# dc26_maneki-neko_badge_page01_20180626.net
KiCad netlist of a schematic drawn in EAGLE
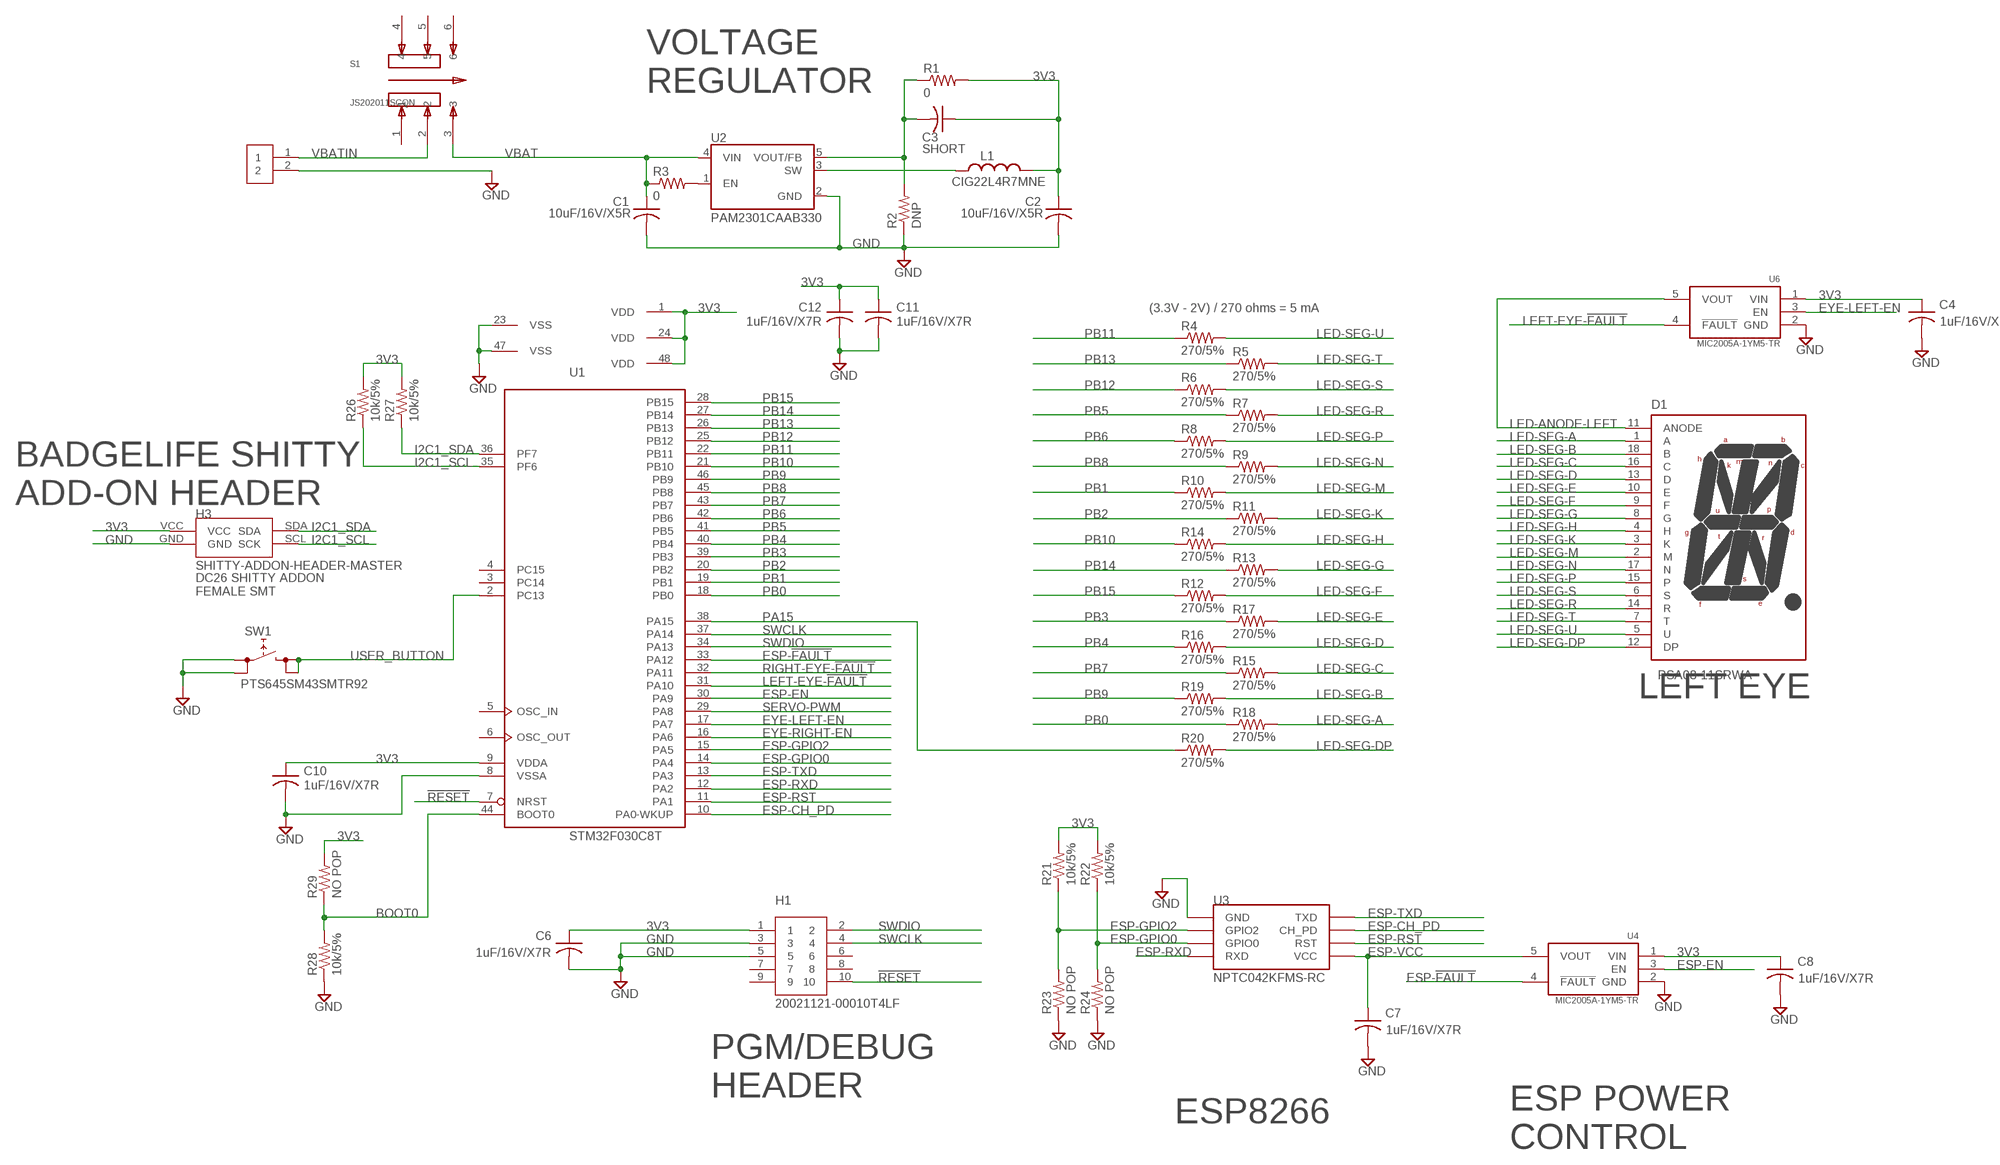
[diagram p0: schematic, sheet 1, part 1 of 2]
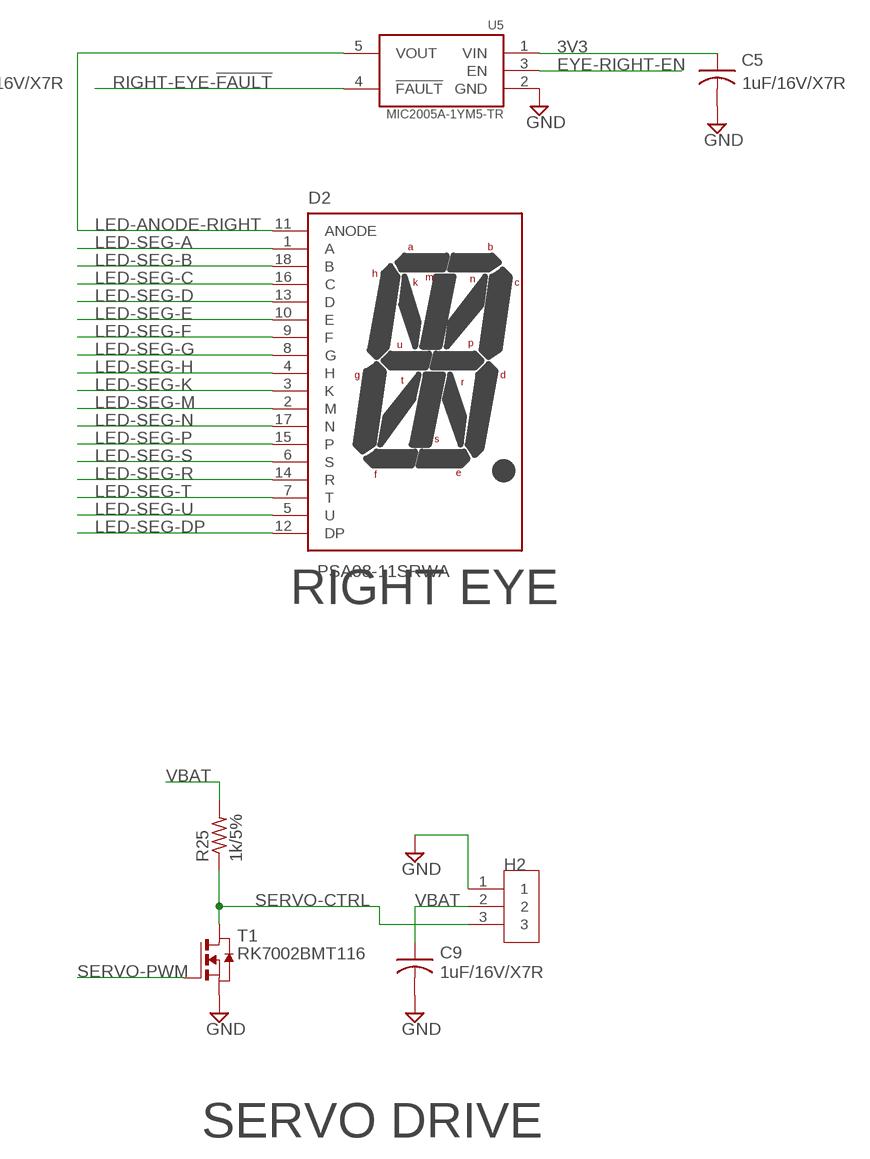
[diagram p1: schematic, sheet 1, part 2 of 2]

(export (version "E")
  (design (tool "Eeschema 10.0.6"))
  (components
    (comp (ref "C1")
      (value "10uF/16V/X5R")
      (footprint "eagle-import:C0805")
      (libsource (lib "eagle-import") (part "C-USC0805"))
    )
    (comp (ref "C2")
      (value "10uF/16V/X5R")
      (footprint "eagle-import:C0805")
      (libsource (lib "eagle-import") (part "C-USC0805"))
    )
    (comp (ref "C3")
      (value "SHORT")
      (footprint "eagle-import:C0805")
      (libsource (lib "eagle-import") (part "C-USC0805"))
    )
    (comp (ref "C4")
      (value "1uF/16V/X7R")
      (footprint "eagle-import:C0805")
      (libsource (lib "eagle-import") (part "C-USC0805"))
    )
    (comp (ref "C5")
      (value "1uF/16V/X7R")
      (footprint "eagle-import:C0805")
      (libsource (lib "eagle-import") (part "C-USC0805"))
    )
    (comp (ref "C6")
      (value "1uF/16V/X7R")
      (footprint "eagle-import:C0805")
      (libsource (lib "eagle-import") (part "C-USC0805"))
    )
    (comp (ref "C7")
      (value "1uF/16V/X7R")
      (footprint "eagle-import:C0805")
      (libsource (lib "eagle-import") (part "C-USC0805"))
    )
    (comp (ref "C8")
      (value "1uF/16V/X7R")
      (footprint "eagle-import:C0805")
      (libsource (lib "eagle-import") (part "C-USC0805"))
    )
    (comp (ref "C9")
      (value "1uF/16V/X7R")
      (footprint "eagle-import:C0805")
      (libsource (lib "eagle-import") (part "C-USC0805"))
    )
    (comp (ref "C10")
      (value "1uF/16V/X7R")
      (footprint "eagle-import:C0805")
      (libsource (lib "eagle-import") (part "C-USC0805"))
    )
    (comp (ref "C11")
      (value "1uF/16V/X7R")
      (footprint "eagle-import:C0805")
      (libsource (lib "eagle-import") (part "C-USC0805"))
    )
    (comp (ref "C12")
      (value "1uF/16V/X7R")
      (footprint "eagle-import:C0805")
      (libsource (lib "eagle-import") (part "C-USC0805"))
    )
    (comp (ref "D1")
      (value "PSA08-11SRWA")
      (footprint "eagle-import:PSA08-11SRWA")
      (libsource (lib "eagle-import") (part "PSA08-11SRWA"))
    )
    (comp (ref "D2")
      (value "PSA08-11SRWA")
      (footprint "eagle-import:PSA08-11SRWA")
      (libsource (lib "eagle-import") (part "PSA08-11SRWA"))
    )
    (comp (ref "H1")
      (value "20021121-00010T4LF")
      (footprint "eagle-import:20021121-00010T4LF")
      (libsource (lib "eagle-import") (part "20021121-00010T4LF"))
    )
    (comp (ref "H2")
      (value "M20-8890345R")
      (footprint "eagle-import:M20-8890345R")
      (libsource (lib "eagle-import") (part "M20-8890345R"))
    )
    (comp (ref "H3")
      (value "SHITTY-ADDON-HEADER-MASTER")
      (footprint "eagle-import:2X2-0.1INCH-FEMALE-SMT")
      (libsource (lib "eagle-import") (part "SHITTY-ADDON-HEADER-MASTER"))
    )
    (comp (ref "L1")
      (value "CIG22L4R7MNE")
      (footprint "eagle-import:L-1008-US")
      (libsource (lib "eagle-import") (part "CIG22L4R7MNE"))
    )
    (comp (ref "R1")
      (value "0")
      (footprint "eagle-import:R0805")
      (libsource (lib "eagle-import") (part "R-US_R0805"))
    )
    (comp (ref "R2")
      (value "DNP")
      (footprint "eagle-import:R0805")
      (libsource (lib "eagle-import") (part "R-US_R0805"))
    )
    (comp (ref "R3")
      (value "0")
      (footprint "eagle-import:R0805")
      (libsource (lib "eagle-import") (part "R-US_R0805"))
    )
    (comp (ref "R4")
      (value "270/5%")
      (footprint "eagle-import:R0805")
      (libsource (lib "eagle-import") (part "R-US_R0805"))
    )
    (comp (ref "R5")
      (value "270/5%")
      (footprint "eagle-import:R0805")
      (libsource (lib "eagle-import") (part "R-US_R0805"))
    )
    (comp (ref "R6")
      (value "270/5%")
      (footprint "eagle-import:R0805")
      (libsource (lib "eagle-import") (part "R-US_R0805"))
    )
    (comp (ref "R7")
      (value "270/5%")
      (footprint "eagle-import:R0805")
      (libsource (lib "eagle-import") (part "R-US_R0805"))
    )
    (comp (ref "R8")
      (value "270/5%")
      (footprint "eagle-import:R0805")
      (libsource (lib "eagle-import") (part "R-US_R0805"))
    )
    (comp (ref "R9")
      (value "270/5%")
      (footprint "eagle-import:R0805")
      (libsource (lib "eagle-import") (part "R-US_R0805"))
    )
    (comp (ref "R10")
      (value "270/5%")
      (footprint "eagle-import:R0805")
      (libsource (lib "eagle-import") (part "R-US_R0805"))
    )
    (comp (ref "R11")
      (value "270/5%")
      (footprint "eagle-import:R0805")
      (libsource (lib "eagle-import") (part "R-US_R0805"))
    )
    (comp (ref "R12")
      (value "270/5%")
      (footprint "eagle-import:R0805")
      (libsource (lib "eagle-import") (part "R-US_R0805"))
    )
    (comp (ref "R13")
      (value "270/5%")
      (footprint "eagle-import:R0805")
      (libsource (lib "eagle-import") (part "R-US_R0805"))
    )
    (comp (ref "R14")
      (value "270/5%")
      (footprint "eagle-import:R0805")
      (libsource (lib "eagle-import") (part "R-US_R0805"))
    )
    (comp (ref "R15")
      (value "270/5%")
      (footprint "eagle-import:R0805")
      (libsource (lib "eagle-import") (part "R-US_R0805"))
    )
    (comp (ref "R16")
      (value "270/5%")
      (footprint "eagle-import:R0805")
      (libsource (lib "eagle-import") (part "R-US_R0805"))
    )
    (comp (ref "R17")
      (value "270/5%")
      (footprint "eagle-import:R0805")
      (libsource (lib "eagle-import") (part "R-US_R0805"))
    )
    (comp (ref "R18")
      (value "270/5%")
      (footprint "eagle-import:R0805")
      (libsource (lib "eagle-import") (part "R-US_R0805"))
    )
    (comp (ref "R19")
      (value "270/5%")
      (footprint "eagle-import:R0805")
      (libsource (lib "eagle-import") (part "R-US_R0805"))
    )
    (comp (ref "R20")
      (value "270/5%")
      (footprint "eagle-import:R0805")
      (libsource (lib "eagle-import") (part "R-US_R0805"))
    )
    (comp (ref "R21")
      (value "10k/5%")
      (footprint "eagle-import:R0805")
      (libsource (lib "eagle-import") (part "R-US_R0805"))
    )
    (comp (ref "R22")
      (value "10k/5%")
      (footprint "eagle-import:R0805")
      (libsource (lib "eagle-import") (part "R-US_R0805"))
    )
    (comp (ref "R23")
      (value "NO POP")
      (footprint "eagle-import:R0805")
      (libsource (lib "eagle-import") (part "R-US_R0805"))
    )
    (comp (ref "R24")
      (value "NO POP")
      (footprint "eagle-import:R0805")
      (libsource (lib "eagle-import") (part "R-US_R0805"))
    )
    (comp (ref "R25")
      (value "1k/5%")
      (footprint "eagle-import:R0805")
      (libsource (lib "eagle-import") (part "R-US_R0805"))
    )
    (comp (ref "R26")
      (value "10k/5%")
      (footprint "eagle-import:R0805")
      (libsource (lib "eagle-import") (part "R-US_R0805"))
    )
    (comp (ref "R27")
      (value "10k/5%")
      (footprint "eagle-import:R0805")
      (libsource (lib "eagle-import") (part "R-US_R0805"))
    )
    (comp (ref "R28")
      (value "10k/5%")
      (footprint "eagle-import:R0805")
      (libsource (lib "eagle-import") (part "R-US_R0805"))
    )
    (comp (ref "R29")
      (value "NO POP")
      (footprint "eagle-import:R0805")
      (libsource (lib "eagle-import") (part "R-US_R0805"))
    )
    (comp (ref "S1")
      (value "JS202011SCQN")
      (footprint "eagle-import:SW_JS202011SCQN")
      (fields (field (name "MF") "C&K Components"))
      (libsource (lib "eagle-import") (part "JS202011SCQN"))
    )
    (comp (ref "SW1")
      (value "PTS645SM43SMTR92")
      (footprint "eagle-import:PTS645SM43SMTR92")
      (libsource (lib "eagle-import") (part "PTS645SM43SMTR92"))
    )
    (comp (ref "T1")
      (value "RK7002BMT116")
      (footprint "eagle-import:SOT-23")
      (libsource (lib "eagle-import") (part "NMOSSOT23"))
    )
    (comp (ref "U$2")
      (value "BATTPADS-SMT")
      (footprint "eagle-import:BATTPADS-SMT")
      (libsource (lib "eagle-import") (part "BATTPADS-SMT"))
    )
    (comp (ref "U1")
      (value "STM32F030C8T")
      (footprint "eagle-import:LQFP48")
      (libsource (lib "eagle-import") (part "STM32F030CT8"))
    )
    (comp (ref "U2")
      (value "PAM2301CAAB330")
      (footprint "eagle-import:SOT95P280X100-5N")
      (libsource (lib "eagle-import") (part "PAM2301CAAB330"))
    )
    (comp (ref "U3")
      (value "NPTC042KFMS-RC")
      (footprint "eagle-import:NPTC042KFMS-RC")
      (libsource (lib "eagle-import") (part "NPTC042KFMS-RC"))
    )
    (comp (ref "U4")
      (value "MIC2005A-1YM5-TR")
      (footprint "eagle-import:SOT95P270X145-5N")
      (libsource (lib "eagle-import") (part "MIC2005A-1YM5-TR"))
    )
    (comp (ref "U5")
      (value "MIC2005A-1YM5-TR")
      (footprint "eagle-import:SOT95P270X145-5N")
      (libsource (lib "eagle-import") (part "MIC2005A-1YM5-TR"))
    )
    (comp (ref "U6")
      (value "MIC2005A-1YM5-TR")
      (footprint "eagle-import:SOT95P270X145-5N")
      (libsource (lib "eagle-import") (part "MIC2005A-1YM5-TR"))
    )
  )
  (nets
    (net (code "1") (name "/3V3") (class "Default")
      (node (ref "C10") (pin "1") (pinfunction "1_1") (pintype "passive"))
      (node (ref "C11") (pin "1") (pinfunction "1_1") (pintype "passive"))
      (node (ref "C12") (pin "1") (pinfunction "1_1") (pintype "passive"))
      (node (ref "C2") (pin "1") (pinfunction "1_1") (pintype "passive"))
      (node (ref "C3") (pin "1") (pinfunction "1_1") (pintype "passive"))
      (node (ref "C4") (pin "1") (pinfunction "1_1") (pintype "passive"))
      (node (ref "C5") (pin "1") (pinfunction "1_1") (pintype "passive"))
      (node (ref "C6") (pin "1") (pinfunction "1_1") (pintype "passive"))
      (node (ref "C8") (pin "1") (pinfunction "1_1") (pintype "passive"))
      (node (ref "H1") (pin "1") (pinfunction "1_1") (pintype "bidirectional"))
      (node (ref "H3") (pin "VCC") (pinfunction "VCC_VCC") (pintype "bidirectional"))
      (node (ref "L1") (pin "P$2") (pinfunction "2_P$2") (pintype "passive"))
      (node (ref "R1") (pin "2") (pinfunction "2_2") (pintype "passive"))
      (node (ref "R21") (pin "2") (pinfunction "2_2") (pintype "passive"))
      (node (ref "R22") (pin "2") (pinfunction "2_2") (pintype "passive"))
      (node (ref "R26") (pin "2") (pinfunction "2_2") (pintype "passive"))
      (node (ref "R27") (pin "2") (pinfunction "2_2") (pintype "passive"))
      (node (ref "R29") (pin "2") (pinfunction "2_2") (pintype "passive"))
      (node (ref "U1") (pin "1") (pinfunction "VDD_1") (pintype "power_in"))
      (node (ref "U1") (pin "24") (pinfunction "VDD_24") (pintype "power_in"))
      (node (ref "U1") (pin "48") (pinfunction "VDD_48") (pintype "power_in"))
      (node (ref "U1") (pin "9") (pinfunction "VDDA_9") (pintype "power_in"))
      (node (ref "U4") (pin "1") (pinfunction "VIN_1") (pintype "bidirectional"))
      (node (ref "U5") (pin "1") (pinfunction "VIN_1") (pintype "bidirectional"))
      (node (ref "U6") (pin "1") (pinfunction "VIN_1") (pintype "bidirectional"))
    )
    (net (code "2") (name "/BOOT0") (class "Default")
      (node (ref "R28") (pin "2") (pinfunction "2_2") (pintype "passive"))
      (node (ref "R29") (pin "1") (pinfunction "1_1") (pintype "passive"))
      (node (ref "U1") (pin "44") (pinfunction "BOOT0_44") (pintype "input"))
    )
    (net (code "3") (name "/ESP-CH_PD") (class "Default")
      (node (ref "U1") (pin "10") (pinfunction "PA0-WKUP_10") (pintype "bidirectional"))
      (node (ref "U3") (pin "3") (pinfunction "CH_PD_3") (pintype "bidirectional"))
    )
    (net (code "4") (name "/ESP-EN") (class "Default")
      (node (ref "U1") (pin "30") (pinfunction "PA9_30") (pintype "bidirectional"))
      (node (ref "U4") (pin "3") (pinfunction "EN_3") (pintype "bidirectional"))
    )
    (net (code "5") (name "/ESP-GPIO0") (class "Default")
      (node (ref "R22") (pin "1") (pinfunction "1_1") (pintype "passive"))
      (node (ref "R24") (pin "2") (pinfunction "2_2") (pintype "passive"))
      (node (ref "U1") (pin "14") (pinfunction "PA4_14") (pintype "bidirectional"))
      (node (ref "U3") (pin "6") (pinfunction "GPIO0_6") (pintype "bidirectional"))
    )
    (net (code "6") (name "/ESP-GPIO2") (class "Default")
      (node (ref "R21") (pin "1") (pinfunction "1_1") (pintype "passive"))
      (node (ref "R23") (pin "2") (pinfunction "2_2") (pintype "passive"))
      (node (ref "U1") (pin "15") (pinfunction "PA5_15") (pintype "bidirectional"))
      (node (ref "U3") (pin "4") (pinfunction "GPIO2_4") (pintype "bidirectional"))
    )
    (net (code "7") (name "/ESP-RST") (class "Default")
      (node (ref "U1") (pin "11") (pinfunction "PA1_11") (pintype "bidirectional"))
      (node (ref "U3") (pin "5") (pinfunction "RST_5") (pintype "bidirectional"))
    )
    (net (code "8") (name "/ESP-RXD") (class "Default")
      (node (ref "U1") (pin "12") (pinfunction "PA2_12") (pintype "bidirectional"))
      (node (ref "U3") (pin "8") (pinfunction "RXD_8") (pintype "bidirectional"))
    )
    (net (code "9") (name "/ESP-TXD") (class "Default")
      (node (ref "U1") (pin "13") (pinfunction "PA3_13") (pintype "bidirectional"))
      (node (ref "U3") (pin "1") (pinfunction "TXD_1") (pintype "bidirectional"))
    )
    (net (code "10") (name "/ESP-VCC") (class "Default")
      (node (ref "C7") (pin "1") (pinfunction "1_1") (pintype "passive"))
      (node (ref "U3") (pin "7") (pinfunction "VCC_7") (pintype "bidirectional"))
      (node (ref "U4") (pin "5") (pinfunction "VOUT_5") (pintype "bidirectional"))
    )
    (net (code "11") (name "/ESP-~{FAULT}") (class "Default")
      (node (ref "U1") (pin "33") (pinfunction "PA12_33") (pintype "bidirectional"))
      (node (ref "U4") (pin "4") (pinfunction "~{FAULT}_4") (pintype "bidirectional"))
    )
    (net (code "12") (name "/EYE-LEFT-EN") (class "Default")
      (node (ref "U1") (pin "17") (pinfunction "PA7_17") (pintype "bidirectional"))
      (node (ref "U6") (pin "3") (pinfunction "EN_3") (pintype "bidirectional"))
    )
    (net (code "13") (name "/EYE-RIGHT-EN") (class "Default")
      (node (ref "U1") (pin "16") (pinfunction "PA6_16") (pintype "bidirectional"))
      (node (ref "U5") (pin "3") (pinfunction "EN_3") (pintype "bidirectional"))
    )
    (net (code "14") (name "/I2C1_SCL") (class "Default")
      (node (ref "H3") (pin "SCL") (pinfunction "SCK_SCL") (pintype "bidirectional"))
      (node (ref "R26") (pin "1") (pinfunction "1_1") (pintype "passive"))
      (node (ref "U1") (pin "35") (pinfunction "PF6_35") (pintype "bidirectional"))
    )
    (net (code "15") (name "/I2C1_SDA") (class "Default")
      (node (ref "H3") (pin "SDA") (pinfunction "SDA_SDA") (pintype "bidirectional"))
      (node (ref "R27") (pin "1") (pinfunction "1_1") (pintype "passive"))
      (node (ref "U1") (pin "36") (pinfunction "PF7_36") (pintype "bidirectional"))
    )
    (net (code "16") (name "/LED-ANODE-LEFT") (class "Default")
      (node (ref "D1") (pin "11") (pinfunction "ANODE_11") (pintype "bidirectional"))
      (node (ref "U6") (pin "5") (pinfunction "VOUT_5") (pintype "bidirectional"))
    )
    (net (code "17") (name "/LED-ANODE-RIGHT") (class "Default")
      (node (ref "D2") (pin "11") (pinfunction "ANODE_11") (pintype "bidirectional"))
      (node (ref "U5") (pin "5") (pinfunction "VOUT_5") (pintype "bidirectional"))
    )
    (net (code "18") (name "/LED-SEG-A") (class "Default")
      (node (ref "D1") (pin "1") (pinfunction "A_1") (pintype "bidirectional"))
      (node (ref "D2") (pin "1") (pinfunction "A_1") (pintype "bidirectional"))
      (node (ref "R18") (pin "2") (pinfunction "2_2") (pintype "passive"))
    )
    (net (code "19") (name "/LED-SEG-B") (class "Default")
      (node (ref "D1") (pin "18") (pinfunction "B_18") (pintype "bidirectional"))
      (node (ref "D2") (pin "18") (pinfunction "B_18") (pintype "bidirectional"))
      (node (ref "R19") (pin "2") (pinfunction "2_2") (pintype "passive"))
    )
    (net (code "20") (name "/LED-SEG-C") (class "Default")
      (node (ref "D1") (pin "16") (pinfunction "C_16") (pintype "bidirectional"))
      (node (ref "D2") (pin "16") (pinfunction "C_16") (pintype "bidirectional"))
      (node (ref "R15") (pin "2") (pinfunction "2_2") (pintype "passive"))
    )
    (net (code "21") (name "/LED-SEG-D") (class "Default")
      (node (ref "D1") (pin "13") (pinfunction "D_13") (pintype "bidirectional"))
      (node (ref "D2") (pin "13") (pinfunction "D_13") (pintype "bidirectional"))
      (node (ref "R16") (pin "2") (pinfunction "2_2") (pintype "passive"))
    )
    (net (code "22") (name "/LED-SEG-DP") (class "Default")
      (node (ref "D1") (pin "12") (pinfunction "DP_12") (pintype "bidirectional"))
      (node (ref "D2") (pin "12") (pinfunction "DP_12") (pintype "bidirectional"))
      (node (ref "R20") (pin "2") (pinfunction "2_2") (pintype "passive"))
    )
    (net (code "23") (name "/LED-SEG-E") (class "Default")
      (node (ref "D1") (pin "10") (pinfunction "E_10") (pintype "bidirectional"))
      (node (ref "D2") (pin "10") (pinfunction "E_10") (pintype "bidirectional"))
      (node (ref "R17") (pin "2") (pinfunction "2_2") (pintype "passive"))
    )
    (net (code "24") (name "/LED-SEG-F") (class "Default")
      (node (ref "D1") (pin "9") (pinfunction "F_9") (pintype "bidirectional"))
      (node (ref "D2") (pin "9") (pinfunction "F_9") (pintype "bidirectional"))
      (node (ref "R12") (pin "2") (pinfunction "2_2") (pintype "passive"))
    )
    (net (code "25") (name "/LED-SEG-G") (class "Default")
      (node (ref "D1") (pin "8") (pinfunction "G_8") (pintype "bidirectional"))
      (node (ref "D2") (pin "8") (pinfunction "G_8") (pintype "bidirectional"))
      (node (ref "R13") (pin "2") (pinfunction "2_2") (pintype "passive"))
    )
    (net (code "26") (name "/LED-SEG-H") (class "Default")
      (node (ref "D1") (pin "4") (pinfunction "H_4") (pintype "bidirectional"))
      (node (ref "D2") (pin "4") (pinfunction "H_4") (pintype "bidirectional"))
      (node (ref "R14") (pin "2") (pinfunction "2_2") (pintype "passive"))
    )
    (net (code "27") (name "/LED-SEG-K") (class "Default")
      (node (ref "D1") (pin "3") (pinfunction "K_3") (pintype "bidirectional"))
      (node (ref "D2") (pin "3") (pinfunction "K_3") (pintype "bidirectional"))
      (node (ref "R11") (pin "2") (pinfunction "2_2") (pintype "passive"))
    )
    (net (code "28") (name "/LED-SEG-M") (class "Default")
      (node (ref "D1") (pin "2") (pinfunction "M_2") (pintype "bidirectional"))
      (node (ref "D2") (pin "2") (pinfunction "M_2") (pintype "bidirectional"))
      (node (ref "R10") (pin "2") (pinfunction "2_2") (pintype "passive"))
    )
    (net (code "29") (name "/LED-SEG-N") (class "Default")
      (node (ref "D1") (pin "17") (pinfunction "N_17") (pintype "bidirectional"))
      (node (ref "D2") (pin "17") (pinfunction "N_17") (pintype "bidirectional"))
      (node (ref "R9") (pin "2") (pinfunction "2_2") (pintype "passive"))
    )
    (net (code "30") (name "/LED-SEG-P") (class "Default")
      (node (ref "D1") (pin "15") (pinfunction "P_15") (pintype "bidirectional"))
      (node (ref "D2") (pin "15") (pinfunction "P_15") (pintype "bidirectional"))
      (node (ref "R8") (pin "2") (pinfunction "2_2") (pintype "passive"))
    )
    (net (code "31") (name "/LED-SEG-R") (class "Default")
      (node (ref "D1") (pin "14") (pinfunction "R_14") (pintype "bidirectional"))
      (node (ref "D2") (pin "14") (pinfunction "R_14") (pintype "bidirectional"))
      (node (ref "R7") (pin "2") (pinfunction "2_2") (pintype "passive"))
    )
    (net (code "32") (name "/LED-SEG-S") (class "Default")
      (node (ref "D1") (pin "6") (pinfunction "S_6") (pintype "bidirectional"))
      (node (ref "D2") (pin "6") (pinfunction "S_6") (pintype "bidirectional"))
      (node (ref "R6") (pin "2") (pinfunction "2_2") (pintype "passive"))
    )
    (net (code "33") (name "/LED-SEG-T") (class "Default")
      (node (ref "D1") (pin "7") (pinfunction "T_7") (pintype "bidirectional"))
      (node (ref "D2") (pin "7") (pinfunction "T_7") (pintype "bidirectional"))
      (node (ref "R5") (pin "2") (pinfunction "2_2") (pintype "passive"))
    )
    (net (code "34") (name "/LED-SEG-U") (class "Default")
      (node (ref "D1") (pin "5") (pinfunction "U_5") (pintype "bidirectional"))
      (node (ref "D2") (pin "5") (pinfunction "U_5") (pintype "bidirectional"))
      (node (ref "R4") (pin "2") (pinfunction "2_2") (pintype "passive"))
    )
    (net (code "35") (name "/LEFT-EYE-~{FAULT}") (class "Default")
      (node (ref "U1") (pin "31") (pinfunction "PA10_31") (pintype "bidirectional"))
      (node (ref "U6") (pin "4") (pinfunction "~{FAULT}_4") (pintype "bidirectional"))
    )
    (net (code "36") (name "/PA15") (class "Default")
      (node (ref "R20") (pin "1") (pinfunction "1_1") (pintype "passive"))
      (node (ref "U1") (pin "38") (pinfunction "PA15_38") (pintype "bidirectional"))
    )
    (net (code "37") (name "/PB0") (class "Default")
      (node (ref "R18") (pin "1") (pinfunction "1_1") (pintype "passive"))
      (node (ref "U1") (pin "18") (pinfunction "PB0_18") (pintype "bidirectional"))
    )
    (net (code "38") (name "/PB1") (class "Default")
      (node (ref "R10") (pin "1") (pinfunction "1_1") (pintype "passive"))
      (node (ref "U1") (pin "19") (pinfunction "PB1_19") (pintype "bidirectional"))
    )
    (net (code "39") (name "/PB2") (class "Default")
      (node (ref "R11") (pin "1") (pinfunction "1_1") (pintype "passive"))
      (node (ref "U1") (pin "20") (pinfunction "PB2_20") (pintype "bidirectional"))
    )
    (net (code "40") (name "/PB3") (class "Default")
      (node (ref "R17") (pin "1") (pinfunction "1_1") (pintype "passive"))
      (node (ref "U1") (pin "39") (pinfunction "PB3_39") (pintype "bidirectional"))
    )
    (net (code "41") (name "/PB4") (class "Default")
      (node (ref "R16") (pin "1") (pinfunction "1_1") (pintype "passive"))
      (node (ref "U1") (pin "40") (pinfunction "PB4_40") (pintype "bidirectional"))
    )
    (net (code "42") (name "/PB5") (class "Default")
      (node (ref "R7") (pin "1") (pinfunction "1_1") (pintype "passive"))
      (node (ref "U1") (pin "41") (pinfunction "PB5_41") (pintype "bidirectional"))
    )
    (net (code "43") (name "/PB6") (class "Default")
      (node (ref "R8") (pin "1") (pinfunction "1_1") (pintype "passive"))
      (node (ref "U1") (pin "42") (pinfunction "PB6_42") (pintype "bidirectional"))
    )
    (net (code "44") (name "/PB7") (class "Default")
      (node (ref "R15") (pin "1") (pinfunction "1_1") (pintype "passive"))
      (node (ref "U1") (pin "43") (pinfunction "PB7_43") (pintype "bidirectional"))
    )
    (net (code "45") (name "/PB8") (class "Default")
      (node (ref "R9") (pin "1") (pinfunction "1_1") (pintype "passive"))
      (node (ref "U1") (pin "45") (pinfunction "PB8_45") (pintype "bidirectional"))
    )
    (net (code "46") (name "/PB9") (class "Default")
      (node (ref "R19") (pin "1") (pinfunction "1_1") (pintype "passive"))
      (node (ref "U1") (pin "46") (pinfunction "PB9_46") (pintype "bidirectional"))
    )
    (net (code "47") (name "/PB10") (class "Default")
      (node (ref "R14") (pin "1") (pinfunction "1_1") (pintype "passive"))
      (node (ref "U1") (pin "21") (pinfunction "PB10_21") (pintype "bidirectional"))
    )
    (net (code "48") (name "/PB11") (class "Default")
      (node (ref "R4") (pin "1") (pinfunction "1_1") (pintype "passive"))
      (node (ref "U1") (pin "22") (pinfunction "PB11_22") (pintype "bidirectional"))
    )
    (net (code "49") (name "/PB12") (class "Default")
      (node (ref "R6") (pin "1") (pinfunction "1_1") (pintype "passive"))
      (node (ref "U1") (pin "25") (pinfunction "PB12_25") (pintype "bidirectional"))
    )
    (net (code "50") (name "/PB13") (class "Default")
      (node (ref "R5") (pin "1") (pinfunction "1_1") (pintype "passive"))
      (node (ref "U1") (pin "26") (pinfunction "PB13_26") (pintype "bidirectional"))
    )
    (net (code "51") (name "/PB14") (class "Default")
      (node (ref "R13") (pin "1") (pinfunction "1_1") (pintype "passive"))
      (node (ref "U1") (pin "27") (pinfunction "PB14_27") (pintype "bidirectional"))
    )
    (net (code "52") (name "/PB15") (class "Default")
      (node (ref "R12") (pin "1") (pinfunction "1_1") (pintype "passive"))
      (node (ref "U1") (pin "28") (pinfunction "PB15_28") (pintype "bidirectional"))
    )
    (net (code "53") (name "/RIGHT-EYE-~{FAULT}") (class "Default")
      (node (ref "U1") (pin "32") (pinfunction "PA11_32") (pintype "bidirectional"))
      (node (ref "U5") (pin "4") (pinfunction "~{FAULT}_4") (pintype "bidirectional"))
    )
    (net (code "54") (name "/SERVO-CTRL") (class "Default")
      (node (ref "H2") (pin "3") (pinfunction "3_3") (pintype "bidirectional"))
      (node (ref "R25") (pin "1") (pinfunction "1_1") (pintype "passive"))
      (node (ref "T1") (pin "1") (pinfunction "D_1") (pintype "passive"))
    )
    (net (code "55") (name "/SERVO-PWM") (class "Default")
      (node (ref "T1") (pin "3") (pinfunction "G_3") (pintype "passive"))
      (node (ref "U1") (pin "29") (pinfunction "PA8_29") (pintype "bidirectional"))
    )
    (net (code "56") (name "/SWCLK") (class "Default")
      (node (ref "H1") (pin "4") (pinfunction "4_4") (pintype "bidirectional"))
      (node (ref "U1") (pin "37") (pinfunction "PA14_37") (pintype "bidirectional"))
    )
    (net (code "57") (name "/SWDIO") (class "Default")
      (node (ref "H1") (pin "2") (pinfunction "2_2") (pintype "bidirectional"))
      (node (ref "U1") (pin "34") (pinfunction "PA13_34") (pintype "bidirectional"))
    )
    (net (code "58") (name "/USER_BUTTON") (class "Default")
      (node (ref "SW1") (pin "3") (pinfunction "1_3") (pintype "passive"))
      (node (ref "SW1") (pin "4") (pinfunction "1_4") (pintype "passive"))
      (node (ref "U1") (pin "2") (pinfunction "PC13_2") (pintype "bidirectional"))
    )
    (net (code "59") (name "/VBAT") (class "Default")
      (node (ref "C1") (pin "1") (pinfunction "1_1") (pintype "passive"))
      (node (ref "C9") (pin "1") (pinfunction "1_1") (pintype "passive"))
      (node (ref "H2") (pin "2") (pinfunction "2_2") (pintype "bidirectional"))
      (node (ref "R25") (pin "2") (pinfunction "2_2") (pintype "passive"))
      (node (ref "R3") (pin "1") (pinfunction "1_1") (pintype "passive"))
      (node (ref "S1") (pin "3") (pinfunction "3_3") (pintype "passive"))
      (node (ref "U2") (pin "4") (pinfunction "VIN_4") (pintype "input"))
    )
    (net (code "60") (name "/VBATIN") (class "Default")
      (node (ref "S1") (pin "2") (pinfunction "2_2") (pintype "passive"))
      (node (ref "U$2") (pin "1") (pinfunction "1_1") (pintype "bidirectional"))
    )
    (net (code "61") (name "/~{RESET}") (class "Default")
      (node (ref "H1") (pin "10") (pinfunction "10_10") (pintype "bidirectional"))
      (node (ref "U1") (pin "7") (pinfunction "NRST_7") (pintype "bidirectional"))
    )
    (net (code "62") (name "GND") (class "Default")
      (node (ref "C1") (pin "2") (pinfunction "2_2") (pintype "passive"))
      (node (ref "C10") (pin "2") (pinfunction "2_2") (pintype "passive"))
      (node (ref "C11") (pin "2") (pinfunction "2_2") (pintype "passive"))
      (node (ref "C12") (pin "2") (pinfunction "2_2") (pintype "passive"))
      (node (ref "C2") (pin "2") (pinfunction "2_2") (pintype "passive"))
      (node (ref "C4") (pin "2") (pinfunction "2_2") (pintype "passive"))
      (node (ref "C5") (pin "2") (pinfunction "2_2") (pintype "passive"))
      (node (ref "C6") (pin "2") (pinfunction "2_2") (pintype "passive"))
      (node (ref "C7") (pin "2") (pinfunction "2_2") (pintype "passive"))
      (node (ref "C8") (pin "2") (pinfunction "2_2") (pintype "passive"))
      (node (ref "C9") (pin "2") (pinfunction "2_2") (pintype "passive"))
      (node (ref "H1") (pin "3") (pinfunction "3_3") (pintype "bidirectional"))
      (node (ref "H1") (pin "5") (pinfunction "5_5") (pintype "bidirectional"))
      (node (ref "H2") (pin "1") (pinfunction "1_1") (pintype "bidirectional"))
      (node (ref "H3") (pin "GND") (pinfunction "GND_GND") (pintype "bidirectional"))
      (node (ref "R2") (pin "1") (pinfunction "1_1") (pintype "passive"))
      (node (ref "R23") (pin "1") (pinfunction "1_1") (pintype "passive"))
      (node (ref "R24") (pin "1") (pinfunction "1_1") (pintype "passive"))
      (node (ref "R28") (pin "1") (pinfunction "1_1") (pintype "passive"))
      (node (ref "SW1") (pin "1") (pinfunction "0_1") (pintype "passive"))
      (node (ref "SW1") (pin "2") (pinfunction "0_2") (pintype "passive"))
      (node (ref "T1") (pin "2") (pinfunction "S_2") (pintype "passive"))
      (node (ref "U$2") (pin "2") (pinfunction "2_2") (pintype "bidirectional"))
      (node (ref "U1") (pin "23") (pinfunction "VSS_23") (pintype "power_in"))
      (node (ref "U1") (pin "47") (pinfunction "VSS_47") (pintype "power_in"))
      (node (ref "U1") (pin "8") (pinfunction "VSSA_8") (pintype "power_in"))
      (node (ref "U2") (pin "2") (pinfunction "GND_2") (pintype "power_in"))
      (node (ref "U3") (pin "2") (pinfunction "GND_2") (pintype "bidirectional"))
      (node (ref "U4") (pin "2") (pinfunction "GND_2") (pintype "bidirectional"))
      (node (ref "U5") (pin "2") (pinfunction "GND_2") (pintype "bidirectional"))
      (node (ref "U6") (pin "2") (pinfunction "GND_2") (pintype "bidirectional"))
    )
    (net (code "63") (name "Net-(L1-1)") (class "Default")
      (node (ref "L1") (pin "P$1") (pinfunction "1_P$1") (pintype "passive"))
      (node (ref "U2") (pin "3") (pinfunction "SW_3") (pintype "output"))
    )
    (net (code "64") (name "Net-(U2-EN)") (class "Default")
      (node (ref "R3") (pin "2") (pinfunction "2_2") (pintype "passive"))
      (node (ref "U2") (pin "1") (pinfunction "EN_1") (pintype "input"))
    )
    (net (code "65") (name "Net-(U2-VOUT{slash}FB)") (class "Default")
      (node (ref "C3") (pin "2") (pinfunction "2_2") (pintype "passive"))
      (node (ref "R1") (pin "1") (pinfunction "1_1") (pintype "passive"))
      (node (ref "R2") (pin "2") (pinfunction "2_2") (pintype "passive"))
      (node (ref "U2") (pin "5") (pinfunction "VOUT/FB_5") (pintype "output"))
    )
    (net (code "66") (name "unconnected-(H1-Pad6)") (class "Default")
      (node (ref "H1") (pin "6") (pinfunction "6_6") (pintype "bidirectional"))
    )
    (net (code "67") (name "unconnected-(H1-Pad7)") (class "Default")
      (node (ref "H1") (pin "7") (pinfunction "7_7") (pintype "bidirectional"))
    )
    (net (code "68") (name "unconnected-(H1-Pad8)") (class "Default")
      (node (ref "H1") (pin "8") (pinfunction "8_8") (pintype "bidirectional"))
    )
    (net (code "69") (name "unconnected-(H1-Pad9)") (class "Default")
      (node (ref "H1") (pin "9") (pinfunction "9_9") (pintype "bidirectional"))
    )
    (net (code "70") (name "unconnected-(S1-Pad1)") (class "Default")
      (node (ref "S1") (pin "1") (pinfunction "1_1") (pintype "passive"))
    )
    (net (code "71") (name "unconnected-(S1-Pad4)") (class "Default")
      (node (ref "S1") (pin "4") (pinfunction "4_4") (pintype "passive"))
    )
    (net (code "72") (name "unconnected-(S1-Pad5)") (class "Default")
      (node (ref "S1") (pin "5") (pinfunction "5_5") (pintype "passive"))
    )
    (net (code "73") (name "unconnected-(S1-Pad6)") (class "Default")
      (node (ref "S1") (pin "6") (pinfunction "6_6") (pintype "passive"))
    )
    (net (code "74") (name "unconnected-(U1A-OSC_IN-Pad5)") (class "Default")
      (node (ref "U1") (pin "5") (pinfunction "OSC_IN_5") (pintype "bidirectional"))
    )
    (net (code "75") (name "unconnected-(U1A-OSC_OUT-Pad6)") (class "Default")
      (node (ref "U1") (pin "6") (pinfunction "OSC_OUT_6") (pintype "bidirectional"))
    )
    (net (code "76") (name "unconnected-(U1A-PC14-Pad3)") (class "Default")
      (node (ref "U1") (pin "3") (pinfunction "PC14_3") (pintype "bidirectional"))
    )
    (net (code "77") (name "unconnected-(U1A-PC15-Pad4)") (class "Default")
      (node (ref "U1") (pin "4") (pinfunction "PC15_4") (pintype "bidirectional"))
    )
  )
)
